# PG05_Schematic_Sheet3.net
KiCad netlist of a schematic drawn in Altium Designer
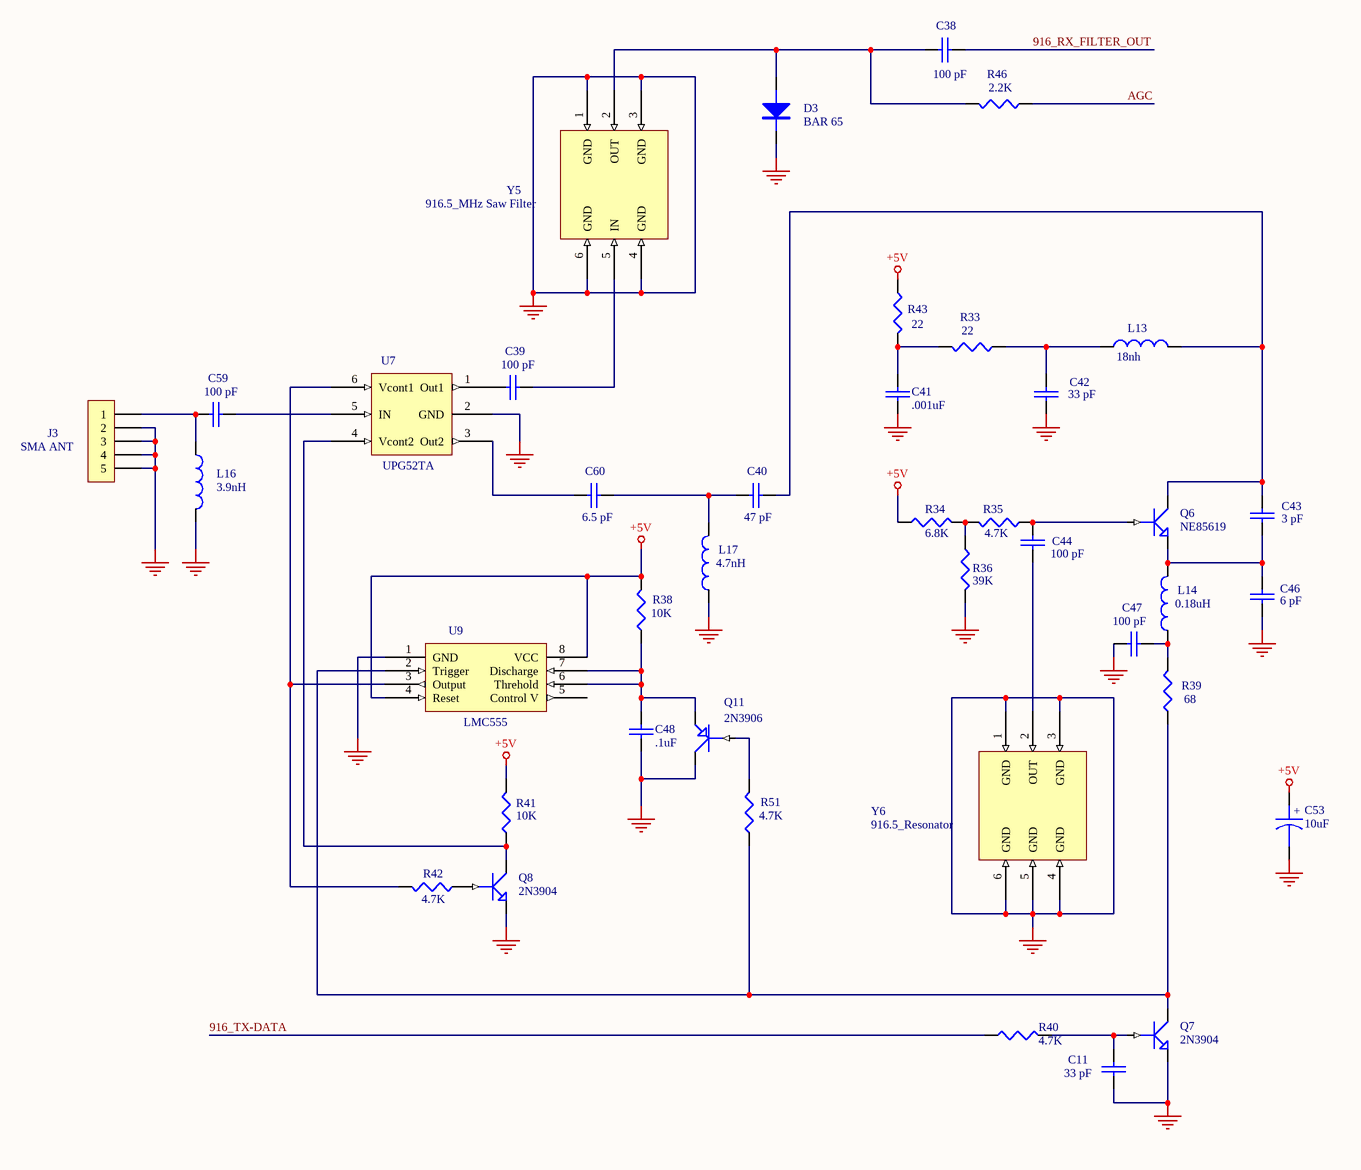
[diagram p0: PG05_Schematic Sheet3.SchDoc]

(export (version "E")
  (design (tool "Eeschema 10.0.6"))
  (components
    (comp (ref "C11")
      (value "33 pF")
      (footprint "0603")
      (description "Capacitor")
      (libsource (lib "*") (part "CAP"))
    )
    (comp (ref "C38")
      (value "100 pF")
      (footprint "0603")
      (description "Capacitor")
      (libsource (lib "*") (part "CAP"))
    )
    (comp (ref "C39")
      (value "100 pF")
      (footprint "0603")
      (description "Capacitor")
      (libsource (lib "*") (part "CAP"))
    )
    (comp (ref "C40")
      (value "47 pF")
      (footprint "0603")
      (description "Capacitor")
      (libsource (lib "*") (part "CAP"))
    )
    (comp (ref "C41")
      (value ".001uF")
      (footprint "0603")
      (description "Capacitor")
      (libsource (lib "*") (part "CAP"))
    )
    (comp (ref "C42")
      (value "33 pF")
      (footprint "0603")
      (description "Capacitor")
      (libsource (lib "*") (part "CAP"))
    )
    (comp (ref "C43")
      (value "3 pF")
      (footprint "0603")
      (description "Capacitor")
      (libsource (lib "*") (part "CAP"))
    )
    (comp (ref "C44")
      (value "100 pF")
      (footprint "0603")
      (description "Capacitor")
      (libsource (lib "*") (part "CAP"))
    )
    (comp (ref "C46")
      (value "6 pF")
      (footprint "0603")
      (description "Capacitor")
      (libsource (lib "*") (part "CAP"))
    )
    (comp (ref "C47")
      (value "100 pF")
      (footprint "0603")
      (description "Capacitor")
      (libsource (lib "*") (part "CAP"))
    )
    (comp (ref "C48")
      (value ".1uF")
      (footprint "0603")
      (description "Capacitor")
      (libsource (lib "*") (part "CAP"))
    )
    (comp (ref "C53")
      (value "10uF")
      (footprint "CAP A CASE")
      (description "Capacitor")
      (libsource (lib "*") (part "CAPACITOR POL"))
    )
    (comp (ref "C59")
      (value "100 pF")
      (footprint "0603")
      (description "Capacitor")
      (libsource (lib "*") (part "CAP"))
    )
    (comp (ref "C60")
      (value "6.5 pF")
      (footprint "0603")
      (description "Capacitor")
      (libsource (lib "*") (part "CAP"))
    )
    (comp (ref "D3")
      (value "BAR 65")
      (footprint "DIODE SC79")
      (description "Diode")
      (libsource (lib "*") (part "DIODE"))
    )
    (comp (ref "J3")
      (value "SMA ANT")
      (footprint "50 OHM ANT")
      (description "Connector")
      (libsource (lib "*") (part "CON5"))
    )
    (comp (ref "L13")
      (value "18nh")
      (footprint "0603")
      (description "INDUCTOR 18NH 5% 0603 SMD")
      (fields (field (name "VENDORPARTNUMBER") "PCD1976TR-ND") (field (name "MFG") "Panasdonic"))
      (libsource (lib "*") (part "INDUCTOR"))
    )
    (comp (ref "L14") (value "0.18uH") (footprint "0603") (libsource (lib "*") (part "INDUCTOR")))
    (comp (ref "L16") (value "3.9nH") (footprint "0603") (libsource (lib "*") (part "INDUCTOR")))
    (comp (ref "L17") (value "4.7nH") (footprint "0603") (libsource (lib "*") (part "INDUCTOR")))
    (comp (ref "Q6")
      (value "NE85619")
      (footprint "3 PIN ULTRA SUPER MINI MOLD")
      (description "NPN Transistor")
      (libsource (lib "*") (part "NPN1"))
    )
    (comp (ref "Q7")
      (value "2N3904")
      (footprint "SOT23 TRANS")
      (description "NPN Transistor")
      (libsource (lib "*") (part "NPN1"))
    )
    (comp (ref "Q8")
      (value "2N3904")
      (footprint "SOT23 TRANS")
      (description "NPN Transistor")
      (libsource (lib "*") (part "NPN1"))
    )
    (comp (ref "Q11")
      (value "2N3906")
      (footprint "SOT23 TRANS")
      (description "PNP Transistor")
      (libsource (lib "*") (part "PNP1"))
    )
    (comp (ref "R33") (value "22") (footprint "0603") (libsource (lib "*") (part "RESISTOR")))
    (comp (ref "R34") (value "6.8K") (footprint "0603") (libsource (lib "*") (part "RESISTOR")))
    (comp (ref "R35") (value "4.7K") (footprint "0603") (libsource (lib "*") (part "RESISTOR")))
    (comp (ref "R36") (value "39K") (footprint "0603") (libsource (lib "*") (part "RESISTOR")))
    (comp (ref "R38") (value "10K") (footprint "0603") (libsource (lib "*") (part "RESISTOR")))
    (comp (ref "R39") (value "68") (footprint "0603") (libsource (lib "*") (part "RESISTOR")))
    (comp (ref "R40") (value "4.7K") (footprint "0603") (libsource (lib "*") (part "RESISTOR")))
    (comp (ref "R41") (value "10K") (footprint "0603") (libsource (lib "*") (part "RESISTOR")))
    (comp (ref "R42") (value "4.7K") (footprint "0603") (libsource (lib "*") (part "RESISTOR")))
    (comp (ref "R43") (value "22") (footprint "0603") (libsource (lib "*") (part "RESISTOR")))
    (comp (ref "R46") (value "2.2K") (footprint "0603") (libsource (lib "*") (part "RESISTOR")))
    (comp (ref "R51") (value "4.7K") (footprint "0603") (libsource (lib "*") (part "RESISTOR")))
    (comp (ref "U7") (value "UPG52TA") (footprint "TO6") (libsource (lib "*") (part "UPG152TA_0")))
    (comp (ref "U9") (value "LMC555") (footprint "SO8 SMALL") (libsource (lib "*") (part "LMC555")))
    (comp (ref "Y5") (value "916.5_MHz Saw Filter") (libsource (lib "*") (part "RESONATOR3")))
    (comp (ref "Y6")
      (value "916.5_Resonator")
      (footprint "RESONATOR2")
      (libsource (lib "*") (part "RESONATOR2"))
    )
  )
  (nets
    (net (code "1") (name "+5V") (class "Default")
      (node (ref "C53") (pin "1") (pinfunction "1_1") (pintype "passive"))
      (node (ref "R34") (pin "1") (pinfunction "1_1") (pintype "passive"))
      (node (ref "R38") (pin "2") (pinfunction "2_2") (pintype "passive"))
      (node (ref "R41") (pin "2") (pinfunction "2_2") (pintype "passive"))
      (node (ref "R43") (pin "1") (pinfunction "1_1") (pintype "passive"))
      (node (ref "U9") (pin "4") (pinfunction "Reset_4") (pintype "input"))
      (node (ref "U9") (pin "8") (pinfunction "VCC_8") (pintype "power_in"))
    )
    (net (code "2") (name "/916_RX_FILTER_OUT") (class "Default")
      (node (ref "C38") (pin "2") (pinfunction "2_2") (pintype "passive"))
    )
    (net (code "3") (name "/916_TX-DATA") (class "Default")
      (node (ref "R40") (pin "1") (pinfunction "1_1") (pintype "passive"))
    )
    (net (code "4") (name "/AGC") (class "Default")
      (node (ref "R46") (pin "1") (pinfunction "1_1") (pintype "passive"))
    )
    (net (code "5") (name "GND_SIGNAL") (class "Default")
      (node (ref "C11") (pin "2") (pinfunction "2_2") (pintype "passive"))
      (node (ref "C41") (pin "2") (pinfunction "2_2") (pintype "passive"))
      (node (ref "C42") (pin "2") (pinfunction "2_2") (pintype "passive"))
      (node (ref "C46") (pin "2") (pinfunction "2_2") (pintype "passive"))
      (node (ref "C47") (pin "1") (pinfunction "1_1") (pintype "passive"))
      (node (ref "C48") (pin "2") (pinfunction "2_2") (pintype "passive"))
      (node (ref "C53") (pin "2") (pinfunction "2_2") (pintype "passive"))
      (node (ref "D3") (pin "K") (pinfunction "K_K") (pintype "passive"))
      (node (ref "J3") (pin "2") (pinfunction "2_2") (pintype "passive"))
      (node (ref "J3") (pin "3") (pinfunction "3_3") (pintype "passive"))
      (node (ref "J3") (pin "4") (pinfunction "4_4") (pintype "passive"))
      (node (ref "J3") (pin "5") (pinfunction "5_5") (pintype "passive"))
      (node (ref "L16") (pin "2") (pinfunction "2_2") (pintype "passive"))
      (node (ref "L17") (pin "1") (pinfunction "1_1") (pintype "passive"))
      (node (ref "Q11") (pin "C") (pinfunction "C_C") (pintype "passive"))
      (node (ref "Q7") (pin "E") (pinfunction "E_E") (pintype "passive"))
      (node (ref "Q8") (pin "E") (pinfunction "E_E") (pintype "passive"))
      (node (ref "R36") (pin "2") (pinfunction "2_2") (pintype "passive"))
      (node (ref "U7") (pin "2") (pinfunction "GND_2") (pintype "power_in"))
      (node (ref "U9") (pin "1") (pinfunction "GND_1") (pintype "power_in"))
      (node (ref "Y5") (pin "1") (pinfunction "GND_1") (pintype "input"))
      (node (ref "Y5") (pin "3") (pinfunction "GND_3") (pintype "input"))
      (node (ref "Y5") (pin "4") (pinfunction "GND_4") (pintype "input"))
      (node (ref "Y5") (pin "6") (pinfunction "GND_6") (pintype "input"))
      (node (ref "Y6") (pin "1") (pinfunction "GND_1") (pintype "input"))
      (node (ref "Y6") (pin "3") (pinfunction "GND_3") (pintype "input"))
      (node (ref "Y6") (pin "4") (pinfunction "GND_4") (pintype "input"))
      (node (ref "Y6") (pin "5") (pinfunction "GND_5") (pintype "input"))
      (node (ref "Y6") (pin "6") (pinfunction "GND_6") (pintype "input"))
    )
    (net (code "6") (name "Net-(C11-Pad1)") (class "Default")
      (node (ref "C11") (pin "1") (pinfunction "1_1") (pintype "passive"))
      (node (ref "Q7") (pin "B") (pinfunction "B_B") (pintype "input"))
      (node (ref "R40") (pin "2") (pinfunction "2_2") (pintype "passive"))
    )
    (net (code "7") (name "Net-(C40-Pad1)") (class "Default")
      (node (ref "C40") (pin "1") (pinfunction "1_1") (pintype "passive"))
      (node (ref "C60") (pin "2") (pinfunction "2_2") (pintype "passive"))
      (node (ref "L17") (pin "2") (pinfunction "2_2") (pintype "passive"))
    )
    (net (code "8") (name "Net-(C40-Pad2)") (class "Default")
      (node (ref "C40") (pin "2") (pinfunction "2_2") (pintype "passive"))
      (node (ref "C43") (pin "1") (pinfunction "1_1") (pintype "passive"))
      (node (ref "L13") (pin "2") (pinfunction "2_2") (pintype "passive"))
      (node (ref "Q6") (pin "C") (pinfunction "C_C") (pintype "passive"))
    )
    (net (code "9") (name "Net-(C41-Pad1)") (class "Default")
      (node (ref "C41") (pin "1") (pinfunction "1_1") (pintype "passive"))
      (node (ref "R33") (pin "2") (pinfunction "2_2") (pintype "passive"))
      (node (ref "R43") (pin "2") (pinfunction "2_2") (pintype "passive"))
    )
    (net (code "10") (name "Net-(C42-Pad1)") (class "Default")
      (node (ref "C42") (pin "1") (pinfunction "1_1") (pintype "passive"))
      (node (ref "L13") (pin "1") (pinfunction "1_1") (pintype "passive"))
      (node (ref "R33") (pin "1") (pinfunction "1_1") (pintype "passive"))
    )
    (net (code "11") (name "Net-(C43-Pad2)") (class "Default")
      (node (ref "C43") (pin "2") (pinfunction "2_2") (pintype "passive"))
      (node (ref "C46") (pin "1") (pinfunction "1_1") (pintype "passive"))
      (node (ref "L14") (pin "2") (pinfunction "2_2") (pintype "passive"))
      (node (ref "Q6") (pin "E") (pinfunction "E_E") (pintype "passive"))
    )
    (net (code "12") (name "Net-(C44-Pad1)") (class "Default")
      (node (ref "C44") (pin "1") (pinfunction "1_1") (pintype "passive"))
      (node (ref "Q6") (pin "B") (pinfunction "B_B") (pintype "input"))
      (node (ref "R35") (pin "1") (pinfunction "1_1") (pintype "passive"))
    )
    (net (code "13") (name "Net-(C47-Pad2)") (class "Default")
      (node (ref "C47") (pin "2") (pinfunction "2_2") (pintype "passive"))
      (node (ref "L14") (pin "1") (pinfunction "1_1") (pintype "passive"))
      (node (ref "R39") (pin "2") (pinfunction "2_2") (pintype "passive"))
    )
    (net (code "14") (name "Net-(C59-Pad1)") (class "Default")
      (node (ref "C59") (pin "1") (pinfunction "1_1") (pintype "passive"))
      (node (ref "J3") (pin "1") (pinfunction "1_1") (pintype "passive"))
      (node (ref "L16") (pin "1") (pinfunction "1_1") (pintype "passive"))
    )
    (net (code "15") (name "Net-(Q8-PadB)") (class "Default")
      (node (ref "Q8") (pin "B") (pinfunction "B_B") (pintype "input"))
      (node (ref "R42") (pin "1") (pinfunction "1_1") (pintype "passive"))
    )
    (net (code "16") (name "Net-(Q11-PadB)") (class "Default")
      (node (ref "Q11") (pin "B") (pinfunction "B_B") (pintype "input"))
      (node (ref "R51") (pin "2") (pinfunction "2_2") (pintype "passive"))
    )
    (net (code "17") (name "Net-(R34-Pad2)") (class "Default")
      (node (ref "R34") (pin "2") (pinfunction "2_2") (pintype "passive"))
      (node (ref "R35") (pin "2") (pinfunction "2_2") (pintype "passive"))
      (node (ref "R36") (pin "1") (pinfunction "1_1") (pintype "passive"))
    )
    (net (code "18") (name "Net-(U7-IN)") (class "Default")
      (node (ref "C59") (pin "2") (pinfunction "2_2") (pintype "passive"))
      (node (ref "U7") (pin "5") (pinfunction "IN_5") (pintype "input"))
    )
    (net (code "19") (name "Net-(U7-Out1)") (class "Default")
      (node (ref "C39") (pin "1") (pinfunction "1_1") (pintype "passive"))
      (node (ref "U7") (pin "1") (pinfunction "Out1_1") (pintype "output"))
    )
    (net (code "20") (name "Net-(U7-Out2)") (class "Default")
      (node (ref "C60") (pin "1") (pinfunction "1_1") (pintype "passive"))
      (node (ref "U7") (pin "3") (pinfunction "Out2_3") (pintype "output"))
    )
    (net (code "21") (name "Net-(U7-Vcont1)") (class "Default")
      (node (ref "R42") (pin "2") (pinfunction "2_2") (pintype "passive"))
      (node (ref "U7") (pin "6") (pinfunction "Vcont1_6") (pintype "input"))
      (node (ref "U9") (pin "3") (pinfunction "Output_3") (pintype "output"))
    )
    (net (code "22") (name "Net-(U7-Vcont2)") (class "Default")
      (node (ref "Q8") (pin "C") (pinfunction "C_C") (pintype "passive"))
      (node (ref "R41") (pin "1") (pinfunction "1_1") (pintype "passive"))
      (node (ref "U7") (pin "4") (pinfunction "Vcont2_4") (pintype "input"))
    )
    (net (code "23") (name "Net-(U9-Discharge)") (class "Default")
      (node (ref "C48") (pin "1") (pinfunction "1_1") (pintype "passive"))
      (node (ref "Q11") (pin "E") (pinfunction "E_E") (pintype "passive"))
      (node (ref "R38") (pin "1") (pinfunction "1_1") (pintype "passive"))
      (node (ref "U9") (pin "6") (pinfunction "Threhold_6") (pintype "input"))
      (node (ref "U9") (pin "7") (pinfunction "Discharge_7") (pintype "input"))
    )
    (net (code "24") (name "Net-(U9-Trigger)") (class "Default")
      (node (ref "Q7") (pin "C") (pinfunction "C_C") (pintype "passive"))
      (node (ref "R39") (pin "1") (pinfunction "1_1") (pintype "passive"))
      (node (ref "R51") (pin "1") (pinfunction "1_1") (pintype "passive"))
      (node (ref "U9") (pin "2") (pinfunction "Trigger_2") (pintype "input"))
    )
    (net (code "25") (name "Net-(Y5-IN)") (class "Default")
      (node (ref "C39") (pin "2") (pinfunction "2_2") (pintype "passive"))
      (node (ref "Y5") (pin "5") (pinfunction "IN_5") (pintype "input"))
    )
    (net (code "26") (name "Net-(Y5-OUT)") (class "Default")
      (node (ref "C38") (pin "1") (pinfunction "1_1") (pintype "passive"))
      (node (ref "D3") (pin "A") (pinfunction "A_A") (pintype "passive"))
      (node (ref "R46") (pin "2") (pinfunction "2_2") (pintype "passive"))
      (node (ref "Y5") (pin "2") (pinfunction "OUT_2") (pintype "input"))
    )
    (net (code "27") (name "Net-(Y6-OUT)") (class "Default")
      (node (ref "C44") (pin "2") (pinfunction "2_2") (pintype "passive"))
      (node (ref "Y6") (pin "2") (pinfunction "OUT_2") (pintype "input"))
    )
    (net (code "28") (name "unconnected-(U9-Control_V-Pad5)") (class "Default")
      (node (ref "U9") (pin "5") (pinfunction "Control_V_5") (pintype "output"))
    )
  )
)
